# E104-BT5005A.net
KiCad netlist of a schematic drawn in EAGLE
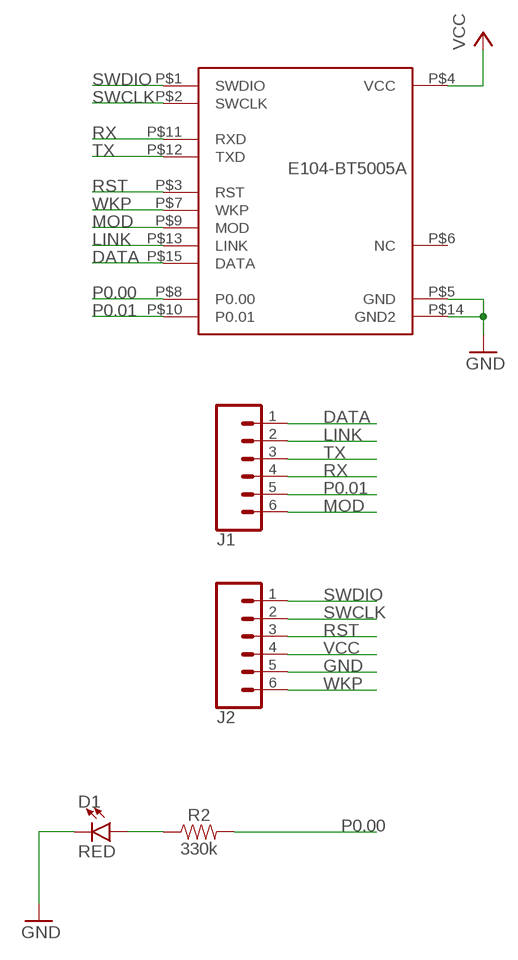
[diagram p0: schematic, sheet 1]

(export (version "E")
  (design (tool "Eeschema 10.0.6"))
  (components
    (comp (ref "D1")
      (value "RED")
      (footprint "eagle-import:LED-0603")
      (libsource (lib "eagle-import") (part "LED-RED0603"))
    )
    (comp (ref "J1")
      (value "CONN_06SILK_FEMALE_PTH")
      (footprint "eagle-import:1X06")
      (libsource (lib "eagle-import") (part "CONN_06SILK_FEMALE_PTH"))
    )
    (comp (ref "J2")
      (value "CONN_06SILK_FEMALE_PTH")
      (footprint "eagle-import:1X06")
      (libsource (lib "eagle-import") (part "CONN_06SILK_FEMALE_PTH"))
    )
    (comp (ref "R2")
      (value "330k")
      (footprint "eagle-import:0603")
      (libsource (lib "eagle-import") (part "330KOHM-0603-1/10W-1%"))
    )
    (comp (ref "U$1")
      (value "E104-BT5005A")
      (footprint "eagle-import:E104-BT5005A")
      (libsource (lib "eagle-import") (part "E104-BT5005A"))
    )
  )
  (nets
    (net (code "1") (name "/DATA") (class "Default")
      (node (ref "J1") (pin "1") (pinfunction "1_1") (pintype "passive"))
      (node (ref "U$1") (pin "P$15") (pinfunction "DATA_P$15") (pintype "bidirectional"))
    )
    (net (code "2") (name "/LINK") (class "Default")
      (node (ref "J1") (pin "2") (pinfunction "2_2") (pintype "passive"))
      (node (ref "U$1") (pin "P$13") (pinfunction "LINK_P$13") (pintype "bidirectional"))
    )
    (net (code "3") (name "/MOD") (class "Default")
      (node (ref "J1") (pin "6") (pinfunction "6_6") (pintype "passive"))
      (node (ref "U$1") (pin "P$9") (pinfunction "MOD_P$9") (pintype "bidirectional"))
    )
    (net (code "4") (name "/P0.00") (class "Default")
      (node (ref "R2") (pin "2") (pinfunction "2_2") (pintype "passive"))
      (node (ref "U$1") (pin "P$8") (pinfunction "P0.00_P$8") (pintype "bidirectional"))
    )
    (net (code "5") (name "/P0.01") (class "Default")
      (node (ref "J1") (pin "5") (pinfunction "5_5") (pintype "passive"))
      (node (ref "U$1") (pin "P$10") (pinfunction "P0.01_P$10") (pintype "bidirectional"))
    )
    (net (code "6") (name "/RST") (class "Default")
      (node (ref "J2") (pin "3") (pinfunction "3_3") (pintype "passive"))
      (node (ref "U$1") (pin "P$3") (pinfunction "RST_P$3") (pintype "bidirectional"))
    )
    (net (code "7") (name "/RX") (class "Default")
      (node (ref "J1") (pin "4") (pinfunction "4_4") (pintype "passive"))
      (node (ref "U$1") (pin "P$11") (pinfunction "RXD_P$11") (pintype "bidirectional"))
    )
    (net (code "8") (name "/SWCLK") (class "Default")
      (node (ref "J2") (pin "2") (pinfunction "2_2") (pintype "passive"))
      (node (ref "U$1") (pin "P$2") (pinfunction "SWCLK_P$2") (pintype "bidirectional"))
    )
    (net (code "9") (name "/SWDIO") (class "Default")
      (node (ref "J2") (pin "1") (pinfunction "1_1") (pintype "passive"))
      (node (ref "U$1") (pin "P$1") (pinfunction "SWDIO_P$1") (pintype "bidirectional"))
    )
    (net (code "10") (name "/TX") (class "Default")
      (node (ref "J1") (pin "3") (pinfunction "3_3") (pintype "passive"))
      (node (ref "U$1") (pin "P$12") (pinfunction "TXD_P$12") (pintype "bidirectional"))
    )
    (net (code "11") (name "/WKP") (class "Default")
      (node (ref "J2") (pin "6") (pinfunction "6_6") (pintype "passive"))
      (node (ref "U$1") (pin "P$7") (pinfunction "WKP_P$7") (pintype "bidirectional"))
    )
    (net (code "12") (name "GND") (class "Default")
      (node (ref "D1") (pin "C") (pinfunction "C_C") (pintype "passive"))
      (node (ref "J2") (pin "5") (pinfunction "5_5") (pintype "passive"))
      (node (ref "U$1") (pin "P$14") (pinfunction "GND2_P$14") (pintype "bidirectional"))
      (node (ref "U$1") (pin "P$5") (pinfunction "GND_P$5") (pintype "bidirectional"))
    )
    (net (code "13") (name "Net-(D1-PadA)") (class "Default")
      (node (ref "D1") (pin "A") (pinfunction "A_A") (pintype "passive"))
      (node (ref "R2") (pin "1") (pinfunction "1_1") (pintype "passive"))
    )
    (net (code "14") (name "VCC") (class "Default")
      (node (ref "J2") (pin "4") (pinfunction "4_4") (pintype "passive"))
      (node (ref "U$1") (pin "P$4") (pinfunction "VCC_P$4") (pintype "bidirectional"))
    )
    (net (code "15") (name "unconnected-(U$1-NC-PadP$6)") (class "Default")
      (node (ref "U$1") (pin "P$6") (pinfunction "NC_P$6") (pintype "bidirectional"))
    )
  )
)
